# 21_RESET_MISC.net
KiCad netlist of a schematic drawn in Altium Designer
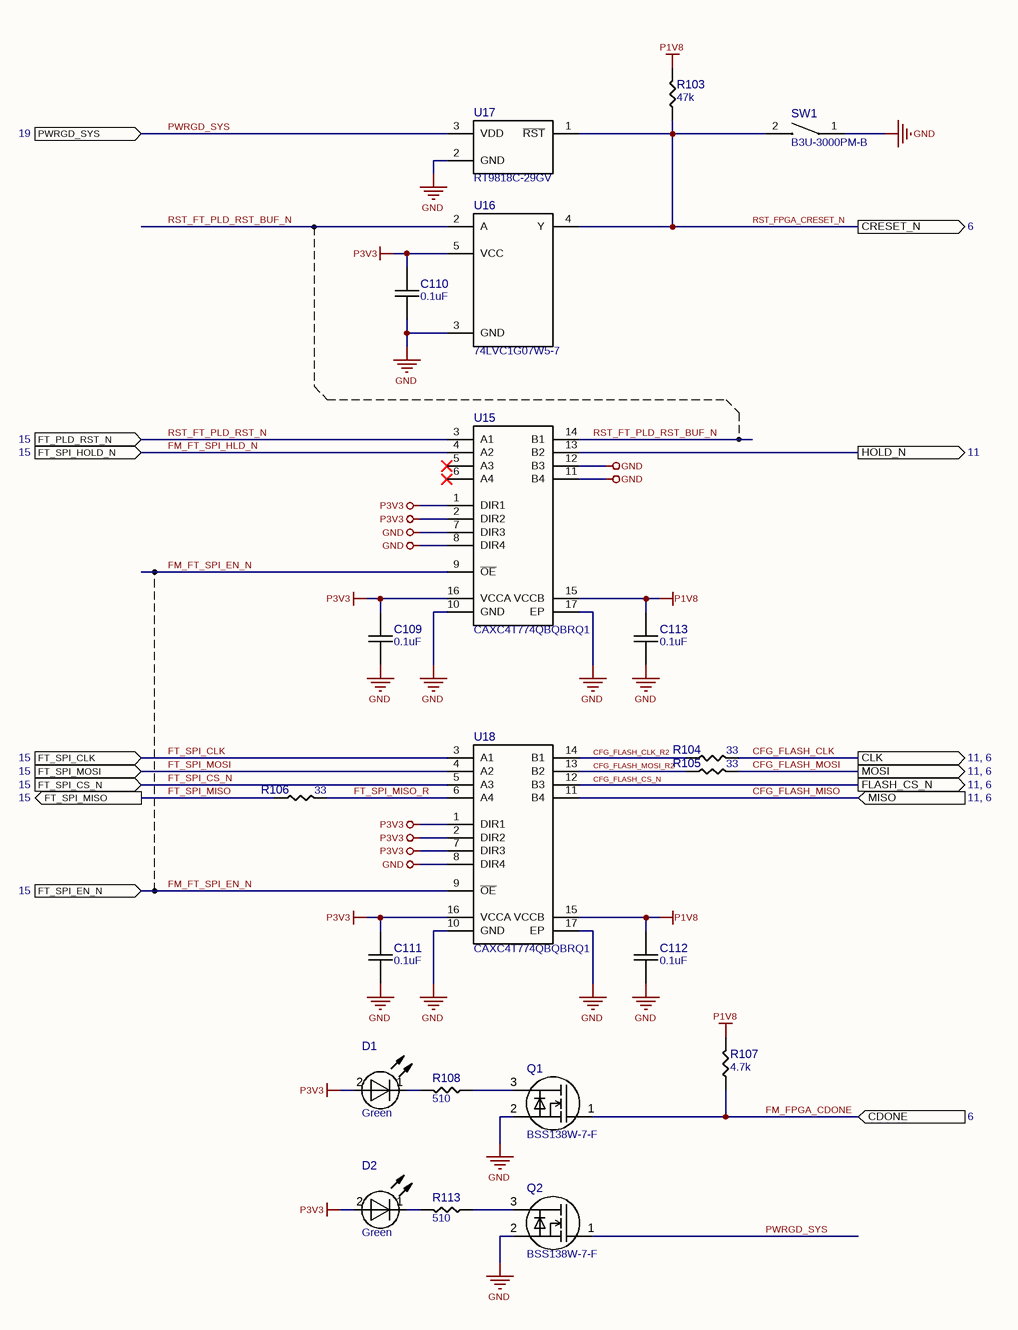
[diagram p0: 21_RESET_MISC.SchDoc]

(export (version "E")
  (design (tool "Eeschema 10.0.6"))
  (components
    (comp (ref "C109")
      (value "0.1uF")
      (footprint "CAPC1005X06N")
      (description "CAP CER 0.1UF 25V X7R 0402")
      (fields (field (name "PART NUMBER") "GRM155R71E104KE14J") (field (name "VOLTAGE") "25V"))
      (libsource (lib "Database") (part "Capacitor"))
    )
    (comp (ref "C110")
      (value "0.1uF")
      (footprint "CAPC1005X06N")
      (description "CAP CER 0.1UF 25V X7R 0402")
      (fields (field (name "PART NUMBER") "GRM155R71E104KE14J") (field (name "VOLTAGE") "25V"))
      (libsource (lib "Database") (part "Capacitor"))
    )
    (comp (ref "C111")
      (value "0.1uF")
      (footprint "CAPC1005X06N")
      (description "CAP CER 0.1UF 25V X7R 0402")
      (fields (field (name "PART NUMBER") "GRM155R71E104KE14J") (field (name "VOLTAGE") "25V"))
      (libsource (lib "Database") (part "Capacitor"))
    )
    (comp (ref "C112")
      (value "0.1uF")
      (footprint "CAPC1005X06N")
      (description "CAP CER 0.1UF 25V X7R 0402")
      (fields (field (name "PART NUMBER") "GRM155R71E104KE14J") (field (name "VOLTAGE") "25V"))
      (libsource (lib "Database") (part "Capacitor"))
    )
    (comp (ref "C113")
      (value "0.1uF")
      (footprint "CAPC1005X06N")
      (description "CAP CER 0.1UF 25V X7R 0402")
      (fields (field (name "PART NUMBER") "GRM155R71E104KE14J") (field (name "VOLTAGE") "25V"))
      (libsource (lib "Database") (part "Capacitor"))
    )
    (comp (ref "D1")
      (value "Green")
      (footprint "LED1608")
      (description "LED GREEN CLEAR CHIP SMD")
      (fields (field (name "PART NUMBER") "APT1608SGC"))
      (libsource (lib "Database") (part "Diode LED"))
    )
    (comp (ref "D2")
      (value "Green")
      (footprint "LED1608")
      (description "LED GREEN CLEAR CHIP SMD")
      (fields (field (name "PART NUMBER") "APT1608SGC"))
      (libsource (lib "Database") (part "Diode LED"))
    )
    (comp (ref "Q1")
      (value "BSS138W-7-F")
      (footprint "SOT65P205X100-3N")
      (description "MOSFET N-CH 50V 200MA SOT323")
      (libsource (lib "Database") (part "Transistor MOSFET-N (GSD)"))
    )
    (comp (ref "Q2")
      (value "BSS138W-7-F")
      (footprint "SOT65P205X100-3N")
      (description "MOSFET N-CH 50V 200MA SOT323")
      (libsource (lib "Database") (part "Transistor MOSFET-N (GSD)"))
    )
    (comp (ref "R103")
      (value "47k")
      (footprint "RESC1005X03N")
      (description "RES SMD 47K OHM 1% 1/16W 0402")
      (fields (field (name "PART NUMBER") "RC0402FR-0747KL"))
      (libsource (lib "Database") (part "Resistor_ENG"))
    )
    (comp (ref "R104")
      (value "33")
      (footprint "RESC1005X03N")
      (description "RES SMD 33 OHM 1% 1/16W 0402")
      (fields (field (name "PART NUMBER") "RC0402FR-0733RL"))
      (libsource (lib "Database") (part "Resistor_ENG"))
    )
    (comp (ref "R105")
      (value "33")
      (footprint "RESC1005X03N")
      (description "RES SMD 33 OHM 1% 1/16W 0402")
      (fields (field (name "PART NUMBER") "RC0402FR-0733RL"))
      (libsource (lib "Database") (part "Resistor_ENG"))
    )
    (comp (ref "R106")
      (value "33")
      (footprint "RESC1005X03N")
      (description "RES SMD 33 OHM 1% 1/16W 0402")
      (fields (field (name "PART NUMBER") "RC0402FR-0733RL"))
      (libsource (lib "Database") (part "Resistor_ENG"))
    )
    (comp (ref "R107")
      (value "4.7k")
      (footprint "RESC1005X03N")
      (description "RES SMD 4.7K OHM 1% 1/16W 0402")
      (fields (field (name "PART NUMBER") "RC0402FR-074K7L"))
      (libsource (lib "Database") (part "Resistor_ENG"))
    )
    (comp (ref "R108")
      (value "510")
      (footprint "RESC1005X03N")
      (description "RES 510 OHM 5% 1/16W 0402")
      (fields (field (name "PART NUMBER") "RC0402JR-07510RL"))
      (libsource (lib "Database") (part "Resistor_ENG"))
    )
    (comp (ref "R113")
      (value "510")
      (footprint "RESC1005X03N")
      (description "RES 510 OHM 5% 1/16W 0402")
      (fields (field (name "PART NUMBER") "RC0402JR-07510RL"))
      (libsource (lib "Database") (part "Resistor_ENG"))
    )
    (comp (ref "SW1")
      (value "B3U-3000PM-B")
      (footprint "B3U-3000P(M)-B")
      (description "SWITCH TACTILE SPST-NO 0.05A 12V")
      (libsource (lib "Database") (part "SW SPST 2 LEADS"))
    )
    (comp (ref "U15")
      (value "CAXC4T774QBQBRQ1")
      (description "AUTOMOTIVE 4-BIT 2-SUPPLY BUS TR")
      (libsource (lib "Database") (part "SN74AXC4T774_BQB"))
    )
    (comp (ref "U16")
      (value "74LVC1G07W5-7")
      (footprint "SOT95P280X145-5N")
      (description "IC BUFFER NON-INVERT 5.5V SOT25")
      (libsource (lib "Database") (part "74LVC1G07_SOT"))
    )
    (comp (ref "U17")
      (value "RT9818C-29GV")
      (footprint "SOT95P230X110-3N")
      (description "IC SUPERVISOR 1 CHANNEL SOT23-3")
      (libsource (lib "Database") (part "RT9818C-29GV"))
    )
    (comp (ref "U18")
      (value "CAXC4T774QBQBRQ1")
      (description "AUTOMOTIVE 4-BIT 2-SUPPLY BUS TR")
      (libsource (lib "Database") (part "SN74AXC4T774_BQB"))
    )
  )
  (nets
    (net (code "1") (name "/CFG_FLASH_CLK") (class "Default")
      (node (ref "R104") (pin "2") (pinfunction "2_2") (pintype "passive"))
    )
    (net (code "2") (name "/CFG_FLASH_CLK_R2") (class "Default")
      (node (ref "R104") (pin "1") (pinfunction "1_1") (pintype "passive"))
      (node (ref "U18") (pin "14") (pinfunction "B1_14") (pintype "passive"))
    )
    (net (code "3") (name "/CFG_FLASH_CS_N") (class "Default")
      (node (ref "U18") (pin "12") (pinfunction "B3_12") (pintype "passive"))
    )
    (net (code "4") (name "/CFG_FLASH_MISO") (class "Default")
      (node (ref "U18") (pin "11") (pinfunction "B4_11") (pintype "passive"))
    )
    (net (code "5") (name "/CFG_FLASH_MOSI") (class "Default")
      (node (ref "R105") (pin "2") (pinfunction "2_2") (pintype "passive"))
    )
    (net (code "6") (name "/CFG_FLASH_MOSI_R2") (class "Default")
      (node (ref "R105") (pin "1") (pinfunction "1_1") (pintype "passive"))
      (node (ref "U18") (pin "13") (pinfunction "B2_13") (pintype "passive"))
    )
    (net (code "7") (name "/FM_FPGA_CDONE") (class "Default")
      (node (ref "Q1") (pin "1") (pinfunction "G_1") (pintype "passive"))
      (node (ref "R107") (pin "1") (pinfunction "1_1") (pintype "passive"))
    )
    (net (code "8") (name "/FM_FT_SPI_EN_N") (class "Default")
      (node (ref "U15") (pin "9") (pinfunction "~{OE}_9") (pintype "passive"))
      (node (ref "U18") (pin "9") (pinfunction "~{OE}_9") (pintype "passive"))
    )
    (net (code "9") (name "/FM_FT_SPI_HLD_N") (class "Default")
      (node (ref "U15") (pin "4") (pinfunction "A2_4") (pintype "passive"))
    )
    (net (code "10") (name "/FT_SPI_CLK") (class "Default")
      (node (ref "U18") (pin "3") (pinfunction "A1_3") (pintype "passive"))
    )
    (net (code "11") (name "/FT_SPI_CS_N") (class "Default")
      (node (ref "U18") (pin "5") (pinfunction "A3_5") (pintype "passive"))
    )
    (net (code "12") (name "/FT_SPI_MISO") (class "Default")
      (node (ref "R106") (pin "1") (pinfunction "1_1") (pintype "passive"))
    )
    (net (code "13") (name "/FT_SPI_MISO_R") (class "Default")
      (node (ref "R106") (pin "2") (pinfunction "2_2") (pintype "passive"))
      (node (ref "U18") (pin "6") (pinfunction "A4_6") (pintype "passive"))
    )
    (net (code "14") (name "/FT_SPI_MOSI") (class "Default")
      (node (ref "U18") (pin "4") (pinfunction "A2_4") (pintype "passive"))
    )
    (net (code "15") (name "/HOLD_N") (class "Default")
      (node (ref "U15") (pin "13") (pinfunction "B2_13") (pintype "passive"))
    )
    (net (code "16") (name "/PWRGD_SYS") (class "Default")
      (node (ref "Q2") (pin "1") (pinfunction "G_1") (pintype "passive"))
      (node (ref "U17") (pin "3") (pinfunction "VDD_3") (pintype "passive"))
    )
    (net (code "17") (name "/RST_FPGA_CRESET_N") (class "Default")
      (node (ref "R103") (pin "1") (pinfunction "1_1") (pintype "passive"))
      (node (ref "SW1") (pin "2") (pinfunction "2_2") (pintype "passive"))
      (node (ref "U16") (pin "4") (pinfunction "Y_4") (pintype "passive"))
      (node (ref "U17") (pin "1") (pinfunction "~{RST}_1") (pintype "passive"))
    )
    (net (code "18") (name "/RST_FT_PLD_RST_BUF_N") (class "Default")
      (node (ref "U15") (pin "14") (pinfunction "B1_14") (pintype "passive"))
      (node (ref "U16") (pin "2") (pinfunction "A_2") (pintype "passive"))
    )
    (net (code "19") (name "/RST_FT_PLD_RST_N") (class "Default")
      (node (ref "U15") (pin "3") (pinfunction "A1_3") (pintype "passive"))
    )
    (net (code "20") (name "GND") (class "Default")
      (node (ref "C109") (pin "1") (pinfunction "1_1") (pintype "passive"))
      (node (ref "C110") (pin "1") (pinfunction "1_1") (pintype "passive"))
      (node (ref "C111") (pin "1") (pinfunction "1_1") (pintype "passive"))
      (node (ref "C112") (pin "1") (pinfunction "1_1") (pintype "passive"))
      (node (ref "C113") (pin "1") (pinfunction "1_1") (pintype "passive"))
      (node (ref "Q1") (pin "2") (pinfunction "S_2") (pintype "passive"))
      (node (ref "Q2") (pin "2") (pinfunction "S_2") (pintype "passive"))
      (node (ref "SW1") (pin "1") (pinfunction "1_1") (pintype "passive"))
      (node (ref "U15") (pin "10") (pinfunction "GND_10") (pintype "passive"))
      (node (ref "U15") (pin "11") (pinfunction "B4_11") (pintype "passive"))
      (node (ref "U15") (pin "12") (pinfunction "B3_12") (pintype "passive"))
      (node (ref "U15") (pin "17") (pinfunction "EP_17") (pintype "passive"))
      (node (ref "U15") (pin "7") (pinfunction "DIR3_7") (pintype "passive"))
      (node (ref "U15") (pin "8") (pinfunction "DIR4_8") (pintype "passive"))
      (node (ref "U16") (pin "3") (pinfunction "GND_3") (pintype "passive"))
      (node (ref "U17") (pin "2") (pinfunction "GND_2") (pintype "passive"))
      (node (ref "U18") (pin "10") (pinfunction "GND_10") (pintype "passive"))
      (node (ref "U18") (pin "17") (pinfunction "EP_17") (pintype "passive"))
      (node (ref "U18") (pin "8") (pinfunction "DIR4_8") (pintype "passive"))
    )
    (net (code "21") (name "Net-(D1-C)") (class "Default")
      (node (ref "D1") (pin "1") (pinfunction "C_1") (pintype "passive"))
      (node (ref "R108") (pin "2") (pinfunction "2_2") (pintype "passive"))
    )
    (net (code "22") (name "Net-(D2-C)") (class "Default")
      (node (ref "D2") (pin "1") (pinfunction "C_1") (pintype "passive"))
      (node (ref "R113") (pin "2") (pinfunction "2_2") (pintype "passive"))
    )
    (net (code "23") (name "Net-(Q1-D)") (class "Default")
      (node (ref "Q1") (pin "3") (pinfunction "D_3") (pintype "passive"))
      (node (ref "R108") (pin "1") (pinfunction "1_1") (pintype "passive"))
    )
    (net (code "24") (name "Net-(Q2-D)") (class "Default")
      (node (ref "Q2") (pin "3") (pinfunction "D_3") (pintype "passive"))
      (node (ref "R113") (pin "1") (pinfunction "1_1") (pintype "passive"))
    )
    (net (code "25") (name "P1V8") (class "Default")
      (node (ref "C112") (pin "2") (pinfunction "2_2") (pintype "passive"))
      (node (ref "C113") (pin "2") (pinfunction "2_2") (pintype "passive"))
      (node (ref "R103") (pin "2") (pinfunction "2_2") (pintype "passive"))
      (node (ref "R107") (pin "2") (pinfunction "2_2") (pintype "passive"))
      (node (ref "U15") (pin "15") (pinfunction "VCCB_15") (pintype "passive"))
      (node (ref "U18") (pin "15") (pinfunction "VCCB_15") (pintype "passive"))
    )
    (net (code "26") (name "P3V3") (class "Default")
      (node (ref "C109") (pin "2") (pinfunction "2_2") (pintype "passive"))
      (node (ref "C110") (pin "2") (pinfunction "2_2") (pintype "passive"))
      (node (ref "C111") (pin "2") (pinfunction "2_2") (pintype "passive"))
      (node (ref "D1") (pin "2") (pinfunction "A_2") (pintype "passive"))
      (node (ref "D2") (pin "2") (pinfunction "A_2") (pintype "passive"))
      (node (ref "U15") (pin "1") (pinfunction "DIR1_1") (pintype "passive"))
      (node (ref "U15") (pin "16") (pinfunction "VCCA_16") (pintype "passive"))
      (node (ref "U15") (pin "2") (pinfunction "DIR2_2") (pintype "passive"))
      (node (ref "U16") (pin "5") (pinfunction "VCC_5") (pintype "passive"))
      (node (ref "U18") (pin "1") (pinfunction "DIR1_1") (pintype "passive"))
      (node (ref "U18") (pin "16") (pinfunction "VCCA_16") (pintype "passive"))
      (node (ref "U18") (pin "2") (pinfunction "DIR2_2") (pintype "passive"))
      (node (ref "U18") (pin "7") (pinfunction "DIR3_7") (pintype "passive"))
    )
    (net (code "27") (name "unconnected-(U15-A3-Pad5)") (class "Default")
      (node (ref "U15") (pin "5") (pinfunction "A3_5") (pintype "passive+no_connect"))
    )
    (net (code "28") (name "unconnected-(U15-A4-Pad6)") (class "Default")
      (node (ref "U15") (pin "6") (pinfunction "A4_6") (pintype "passive+no_connect"))
    )
  )
)
